# keyswitch.net
KiCad netlist of a schematic drawn in EAGLE
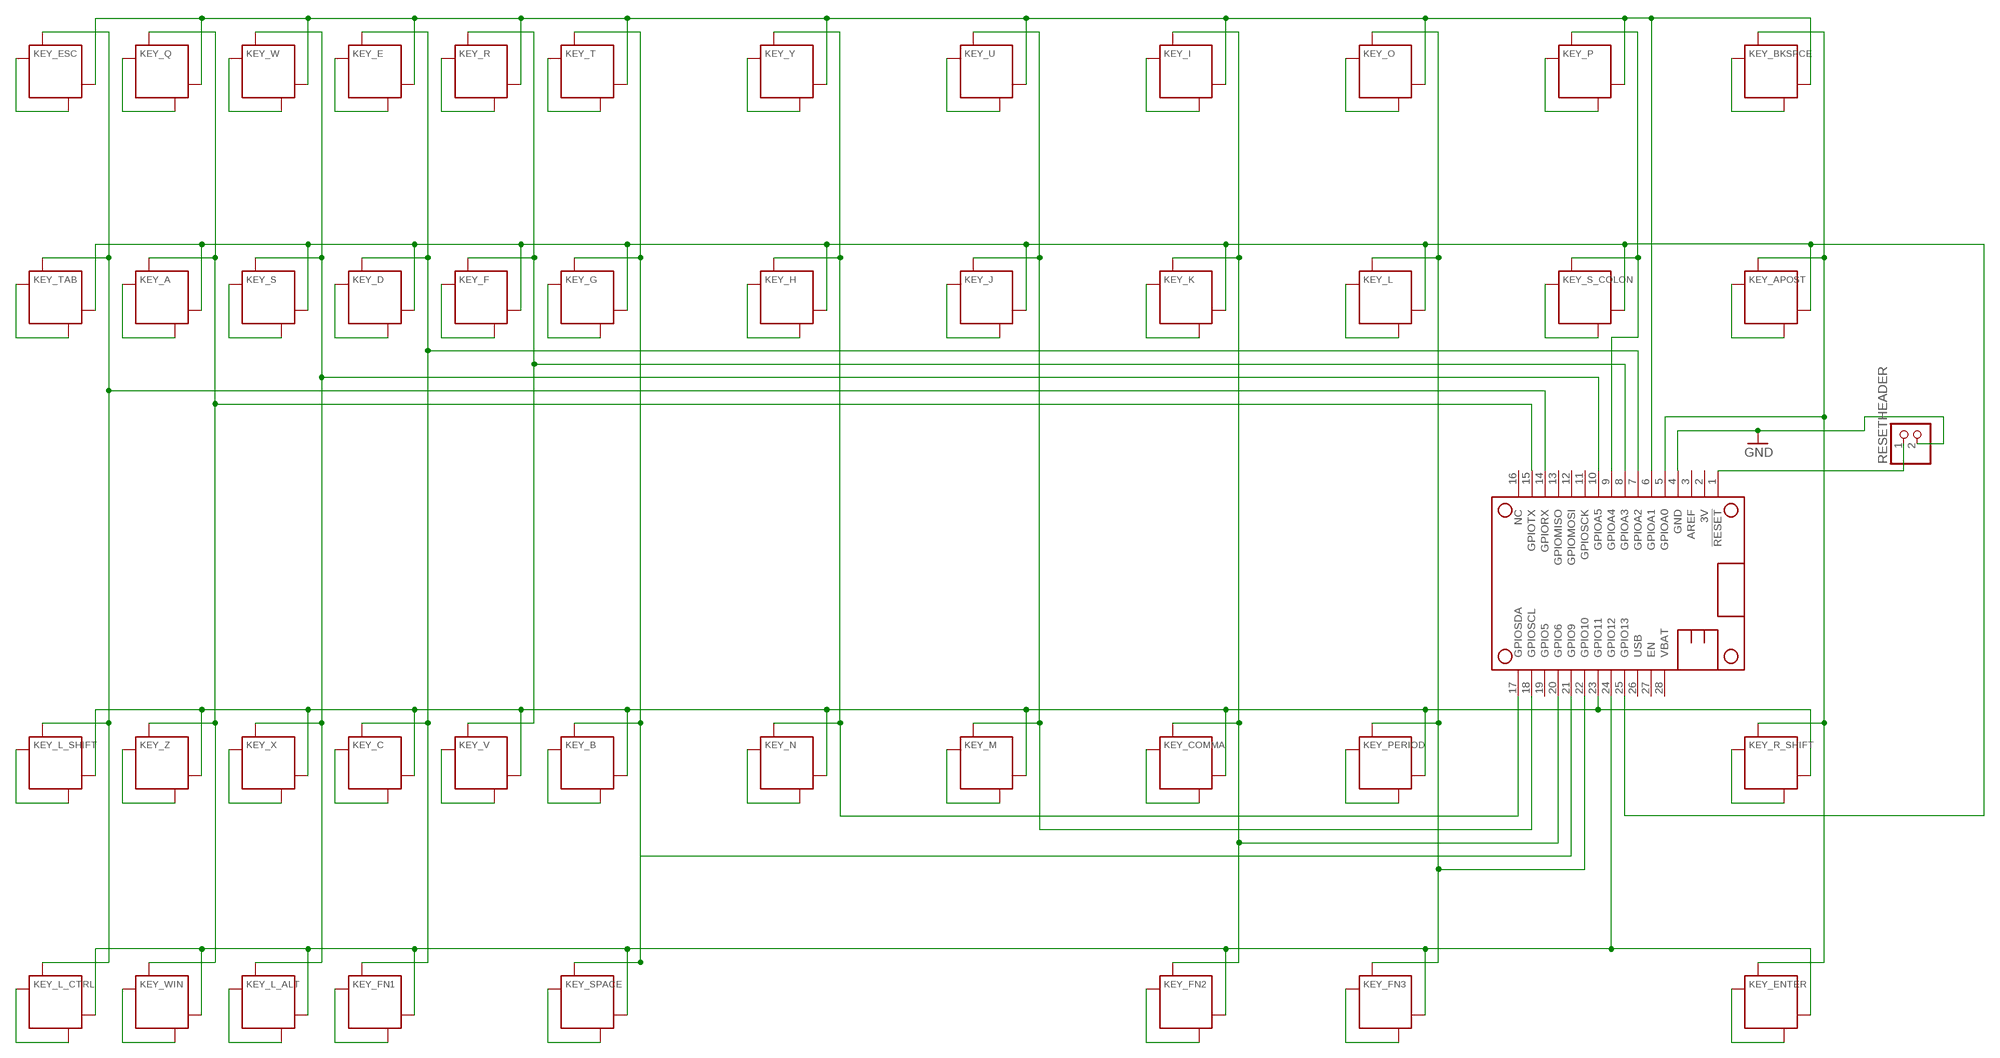
[diagram p0: schematic, sheet 1]

(export (version "E")
  (design (tool "Eeschema 10.0.6"))
  (components
    (comp (ref "FEATHER")
      (value "FEATHERWING_NODIM")
      (footprint "eagle-import:FEATHERWING_DIM")
      (libsource (lib "eagle-import") (part "FEATHERWING_NODIM"))
    )
    (comp (ref "KEY_A")
      (value "KEYSWITCH-DIODE-MX-1U-DIODE")
      (footprint "eagle-import:MX-1U-DIODE")
      (libsource (lib "eagle-import") (part "KEYSWITCH-DIODE-MX-1U-DIODE"))
    )
    (comp (ref "KEY_APOST")
      (value "KEYSWITCH-DIODE-MX-1U-DIODE")
      (footprint "eagle-import:MX-1U-DIODE")
      (libsource (lib "eagle-import") (part "KEYSWITCH-DIODE-MX-1U-DIODE"))
    )
    (comp (ref "KEY_B")
      (value "KEYSWITCH-DIODE-MX-1U-DIODE")
      (footprint "eagle-import:MX-1U-DIODE")
      (libsource (lib "eagle-import") (part "KEYSWITCH-DIODE-MX-1U-DIODE"))
    )
    (comp (ref "KEY_BKSPCE")
      (value "KEYSWITCH-DIODE-MX-1U-DIODE")
      (footprint "eagle-import:MX-1U-DIODE")
      (libsource (lib "eagle-import") (part "KEYSWITCH-DIODE-MX-1U-DIODE"))
    )
    (comp (ref "KEY_C")
      (value "KEYSWITCH-DIODE-MX-1U-DIODE")
      (footprint "eagle-import:MX-1U-DIODE")
      (libsource (lib "eagle-import") (part "KEYSWITCH-DIODE-MX-1U-DIODE"))
    )
    (comp (ref "KEY_COMMA")
      (value "KEYSWITCH-DIODE-MX-1U-DIODE")
      (footprint "eagle-import:MX-1U-DIODE")
      (libsource (lib "eagle-import") (part "KEYSWITCH-DIODE-MX-1U-DIODE"))
    )
    (comp (ref "KEY_D")
      (value "KEYSWITCH-DIODE-MX-1U-DIODE")
      (footprint "eagle-import:MX-1U-DIODE")
      (libsource (lib "eagle-import") (part "KEYSWITCH-DIODE-MX-1U-DIODE"))
    )
    (comp (ref "KEY_E")
      (value "KEYSWITCH-DIODE-MX-1U-DIODE")
      (footprint "eagle-import:MX-1U-DIODE")
      (libsource (lib "eagle-import") (part "KEYSWITCH-DIODE-MX-1U-DIODE"))
    )
    (comp (ref "KEY_ENTER")
      (value "KEYSWITCH-DIODE-MX-1U-DIODE")
      (footprint "eagle-import:MX-1U-DIODE")
      (libsource (lib "eagle-import") (part "KEYSWITCH-DIODE-MX-1U-DIODE"))
    )
    (comp (ref "KEY_ESC")
      (value "KEYSWITCH-DIODE-MX-1U-DIODE")
      (footprint "eagle-import:MX-1U-DIODE")
      (libsource (lib "eagle-import") (part "KEYSWITCH-DIODE-MX-1U-DIODE"))
    )
    (comp (ref "KEY_F")
      (value "KEYSWITCH-DIODE-MX-1U-DIODE")
      (footprint "eagle-import:MX-1U-DIODE")
      (libsource (lib "eagle-import") (part "KEYSWITCH-DIODE-MX-1U-DIODE"))
    )
    (comp (ref "KEY_FN1")
      (value "KEYSWITCH-DIODE-MX-1U-DIODE")
      (footprint "eagle-import:MX-1U-DIODE")
      (libsource (lib "eagle-import") (part "KEYSWITCH-DIODE-MX-1U-DIODE"))
    )
    (comp (ref "KEY_FN2")
      (value "KEYSWITCH-DIODE-MX-1U-DIODE")
      (footprint "eagle-import:MX-1U-DIODE")
      (libsource (lib "eagle-import") (part "KEYSWITCH-DIODE-MX-1U-DIODE"))
    )
    (comp (ref "KEY_FN3")
      (value "KEYSWITCH-DIODE-MX-1U-DIODE")
      (footprint "eagle-import:MX-1U-DIODE")
      (libsource (lib "eagle-import") (part "KEYSWITCH-DIODE-MX-1U-DIODE"))
    )
    (comp (ref "KEY_G")
      (value "KEYSWITCH-DIODE-MX-1U-DIODE")
      (footprint "eagle-import:MX-1U-DIODE")
      (libsource (lib "eagle-import") (part "KEYSWITCH-DIODE-MX-1U-DIODE"))
    )
    (comp (ref "KEY_H")
      (value "KEYSWITCH-DIODE-MX-1U-DIODE")
      (footprint "eagle-import:MX-1U-DIODE")
      (libsource (lib "eagle-import") (part "KEYSWITCH-DIODE-MX-1U-DIODE"))
    )
    (comp (ref "KEY_I")
      (value "KEYSWITCH-DIODE-MX-1U-DIODE")
      (footprint "eagle-import:MX-1U-DIODE")
      (libsource (lib "eagle-import") (part "KEYSWITCH-DIODE-MX-1U-DIODE"))
    )
    (comp (ref "KEY_J")
      (value "KEYSWITCH-DIODE-MX-1U-DIODE")
      (footprint "eagle-import:MX-1U-DIODE")
      (libsource (lib "eagle-import") (part "KEYSWITCH-DIODE-MX-1U-DIODE"))
    )
    (comp (ref "KEY_K")
      (value "KEYSWITCH-DIODE-MX-1U-DIODE")
      (footprint "eagle-import:MX-1U-DIODE")
      (libsource (lib "eagle-import") (part "KEYSWITCH-DIODE-MX-1U-DIODE"))
    )
    (comp (ref "KEY_L")
      (value "KEYSWITCH-DIODE-MX-1U-DIODE")
      (footprint "eagle-import:MX-1U-DIODE")
      (libsource (lib "eagle-import") (part "KEYSWITCH-DIODE-MX-1U-DIODE"))
    )
    (comp (ref "KEY_L_ALT")
      (value "KEYSWITCH-DIODE-MX-1U-DIODE")
      (footprint "eagle-import:MX-1U-DIODE")
      (libsource (lib "eagle-import") (part "KEYSWITCH-DIODE-MX-1U-DIODE"))
    )
    (comp (ref "KEY_L_CTRL")
      (value "KEYSWITCH-DIODE-MX-1U-DIODE")
      (footprint "eagle-import:MX-1U-DIODE")
      (libsource (lib "eagle-import") (part "KEYSWITCH-DIODE-MX-1U-DIODE"))
    )
    (comp (ref "KEY_L_SHIFT")
      (value "KEYSWITCH-DIODE-MX-1U-DIODE")
      (footprint "eagle-import:MX-1U-DIODE")
      (libsource (lib "eagle-import") (part "KEYSWITCH-DIODE-MX-1U-DIODE"))
    )
    (comp (ref "KEY_M")
      (value "KEYSWITCH-DIODE-MX-1U-DIODE")
      (footprint "eagle-import:MX-1U-DIODE")
      (libsource (lib "eagle-import") (part "KEYSWITCH-DIODE-MX-1U-DIODE"))
    )
    (comp (ref "KEY_N")
      (value "KEYSWITCH-DIODE-MX-1U-DIODE")
      (footprint "eagle-import:MX-1U-DIODE")
      (libsource (lib "eagle-import") (part "KEYSWITCH-DIODE-MX-1U-DIODE"))
    )
    (comp (ref "KEY_O")
      (value "KEYSWITCH-DIODE-MX-1U-DIODE")
      (footprint "eagle-import:MX-1U-DIODE")
      (libsource (lib "eagle-import") (part "KEYSWITCH-DIODE-MX-1U-DIODE"))
    )
    (comp (ref "KEY_P")
      (value "KEYSWITCH-DIODE-MX-1U-DIODE")
      (footprint "eagle-import:MX-1U-DIODE")
      (libsource (lib "eagle-import") (part "KEYSWITCH-DIODE-MX-1U-DIODE"))
    )
    (comp (ref "KEY_PERIOD")
      (value "KEYSWITCH-DIODE-MX-1U-DIODE")
      (footprint "eagle-import:MX-1U-DIODE")
      (libsource (lib "eagle-import") (part "KEYSWITCH-DIODE-MX-1U-DIODE"))
    )
    (comp (ref "KEY_Q")
      (value "KEYSWITCH-DIODE-MX-1U-DIODE")
      (footprint "eagle-import:MX-1U-DIODE")
      (libsource (lib "eagle-import") (part "KEYSWITCH-DIODE-MX-1U-DIODE"))
    )
    (comp (ref "KEY_R")
      (value "KEYSWITCH-DIODE-MX-1U-DIODE")
      (footprint "eagle-import:MX-1U-DIODE")
      (libsource (lib "eagle-import") (part "KEYSWITCH-DIODE-MX-1U-DIODE"))
    )
    (comp (ref "KEY_R_SHIFT")
      (value "KEYSWITCH-DIODE-MX-1U-DIODE")
      (footprint "eagle-import:MX-1U-DIODE")
      (libsource (lib "eagle-import") (part "KEYSWITCH-DIODE-MX-1U-DIODE"))
    )
    (comp (ref "KEY_S")
      (value "KEYSWITCH-DIODE-MX-1U-DIODE")
      (footprint "eagle-import:MX-1U-DIODE")
      (libsource (lib "eagle-import") (part "KEYSWITCH-DIODE-MX-1U-DIODE"))
    )
    (comp (ref "KEY_SPACE")
      (value "KEYSWITCH-DIODE-MX-1U-DIODE")
      (footprint "eagle-import:MX-1U-DIODE")
      (libsource (lib "eagle-import") (part "KEYSWITCH-DIODE-MX-1U-DIODE"))
    )
    (comp (ref "KEY_S_COLON")
      (value "KEYSWITCH-DIODE-MX-1U-DIODE")
      (footprint "eagle-import:MX-1U-DIODE")
      (libsource (lib "eagle-import") (part "KEYSWITCH-DIODE-MX-1U-DIODE"))
    )
    (comp (ref "KEY_T")
      (value "KEYSWITCH-DIODE-MX-1U-DIODE")
      (footprint "eagle-import:MX-1U-DIODE")
      (libsource (lib "eagle-import") (part "KEYSWITCH-DIODE-MX-1U-DIODE"))
    )
    (comp (ref "KEY_TAB")
      (value "KEYSWITCH-DIODE-MX-1U-DIODE")
      (footprint "eagle-import:MX-1U-DIODE")
      (libsource (lib "eagle-import") (part "KEYSWITCH-DIODE-MX-1U-DIODE"))
    )
    (comp (ref "KEY_U")
      (value "KEYSWITCH-DIODE-MX-1U-DIODE")
      (footprint "eagle-import:MX-1U-DIODE")
      (libsource (lib "eagle-import") (part "KEYSWITCH-DIODE-MX-1U-DIODE"))
    )
    (comp (ref "KEY_V")
      (value "KEYSWITCH-DIODE-MX-1U-DIODE")
      (footprint "eagle-import:MX-1U-DIODE")
      (libsource (lib "eagle-import") (part "KEYSWITCH-DIODE-MX-1U-DIODE"))
    )
    (comp (ref "KEY_W")
      (value "KEYSWITCH-DIODE-MX-1U-DIODE")
      (footprint "eagle-import:MX-1U-DIODE")
      (libsource (lib "eagle-import") (part "KEYSWITCH-DIODE-MX-1U-DIODE"))
    )
    (comp (ref "KEY_WIN")
      (value "KEYSWITCH-DIODE-MX-1U-DIODE")
      (footprint "eagle-import:MX-1U-DIODE")
      (libsource (lib "eagle-import") (part "KEYSWITCH-DIODE-MX-1U-DIODE"))
    )
    (comp (ref "KEY_X")
      (value "KEYSWITCH-DIODE-MX-1U-DIODE")
      (footprint "eagle-import:MX-1U-DIODE")
      (libsource (lib "eagle-import") (part "KEYSWITCH-DIODE-MX-1U-DIODE"))
    )
    (comp (ref "KEY_Y")
      (value "KEYSWITCH-DIODE-MX-1U-DIODE")
      (footprint "eagle-import:MX-1U-DIODE")
      (libsource (lib "eagle-import") (part "KEYSWITCH-DIODE-MX-1U-DIODE"))
    )
    (comp (ref "KEY_Z")
      (value "KEYSWITCH-DIODE-MX-1U-DIODE")
      (footprint "eagle-import:MX-1U-DIODE")
      (libsource (lib "eagle-import") (part "KEYSWITCH-DIODE-MX-1U-DIODE"))
    )
    (comp (ref "RESETHEADER")
      (value "PINHD-1X2")
      (footprint "eagle-import:1X02")
      (libsource (lib "eagle-import") (part "PINHD-1X2"))
    )
  )
  (nets
    (net (code "1") (name "/3V") (class "Default")
      (node (ref "FEATHER") (pin "2") (pinfunction "3V_2") (pintype "power_in"))
    )
    (net (code "2") (name "/USB") (class "Default")
      (node (ref "FEATHER") (pin "26") (pinfunction "USB_26") (pintype "power_in"))
    )
    (net (code "3") (name "/VBAT") (class "Default")
      (node (ref "FEATHER") (pin "28") (pinfunction "VBAT_28") (pintype "power_in"))
    )
    (net (code "4") (name "GND") (class "Default")
      (node (ref "FEATHER") (pin "4") (pinfunction "GND_4") (pintype "power_in"))
      (node (ref "RESETHEADER") (pin "2") (pinfunction "2_2") (pintype "passive"))
    )
    (net (code "5") (name "Net-(FEATHER-GPIO6)") (class "Default")
      (node (ref "FEATHER") (pin "20") (pinfunction "GPIO6_20") (pintype "bidirectional"))
      (node (ref "KEY_COMMA") (pin "MX2") (pinfunction "P1_MX2") (pintype "bidirectional"))
      (node (ref "KEY_FN2") (pin "MX2") (pinfunction "P1_MX2") (pintype "bidirectional"))
      (node (ref "KEY_I") (pin "MX2") (pinfunction "P1_MX2") (pintype "bidirectional"))
      (node (ref "KEY_K") (pin "MX2") (pinfunction "P1_MX2") (pintype "bidirectional"))
    )
    (net (code "6") (name "Net-(FEATHER-GPIO9)") (class "Default")
      (node (ref "FEATHER") (pin "21") (pinfunction "GPIO9_21") (pintype "bidirectional"))
      (node (ref "KEY_B") (pin "MX2") (pinfunction "P1_MX2") (pintype "bidirectional"))
      (node (ref "KEY_G") (pin "MX2") (pinfunction "P1_MX2") (pintype "bidirectional"))
      (node (ref "KEY_SPACE") (pin "MX2") (pinfunction "P1_MX2") (pintype "bidirectional"))
      (node (ref "KEY_T") (pin "MX2") (pinfunction "P1_MX2") (pintype "bidirectional"))
    )
    (net (code "7") (name "Net-(FEATHER-GPIO10)") (class "Default")
      (node (ref "FEATHER") (pin "22") (pinfunction "GPIO10_22") (pintype "bidirectional"))
      (node (ref "KEY_FN3") (pin "MX2") (pinfunction "P1_MX2") (pintype "bidirectional"))
      (node (ref "KEY_L") (pin "MX2") (pinfunction "P1_MX2") (pintype "bidirectional"))
      (node (ref "KEY_O") (pin "MX2") (pinfunction "P1_MX2") (pintype "bidirectional"))
      (node (ref "KEY_PERIOD") (pin "MX2") (pinfunction "P1_MX2") (pintype "bidirectional"))
    )
    (net (code "8") (name "Net-(FEATHER-GPIO11)") (class "Default")
      (node (ref "FEATHER") (pin "23") (pinfunction "GPIO11_23") (pintype "bidirectional"))
      (node (ref "KEY_B") (pin "D-") (pinfunction "D-_D-") (pintype "bidirectional"))
      (node (ref "KEY_C") (pin "D-") (pinfunction "D-_D-") (pintype "bidirectional"))
      (node (ref "KEY_COMMA") (pin "D-") (pinfunction "D-_D-") (pintype "bidirectional"))
      (node (ref "KEY_L_SHIFT") (pin "D-") (pinfunction "D-_D-") (pintype "bidirectional"))
      (node (ref "KEY_M") (pin "D-") (pinfunction "D-_D-") (pintype "bidirectional"))
      (node (ref "KEY_N") (pin "D-") (pinfunction "D-_D-") (pintype "bidirectional"))
      (node (ref "KEY_PERIOD") (pin "D-") (pinfunction "D-_D-") (pintype "bidirectional"))
      (node (ref "KEY_R_SHIFT") (pin "D-") (pinfunction "D-_D-") (pintype "bidirectional"))
      (node (ref "KEY_V") (pin "D-") (pinfunction "D-_D-") (pintype "bidirectional"))
      (node (ref "KEY_X") (pin "D-") (pinfunction "D-_D-") (pintype "bidirectional"))
      (node (ref "KEY_Z") (pin "D-") (pinfunction "D-_D-") (pintype "bidirectional"))
    )
    (net (code "9") (name "Net-(FEATHER-GPIO12)") (class "Default")
      (node (ref "FEATHER") (pin "24") (pinfunction "GPIO12_24") (pintype "bidirectional"))
      (node (ref "KEY_ENTER") (pin "D-") (pinfunction "D-_D-") (pintype "bidirectional"))
      (node (ref "KEY_FN1") (pin "D-") (pinfunction "D-_D-") (pintype "bidirectional"))
      (node (ref "KEY_FN2") (pin "D-") (pinfunction "D-_D-") (pintype "bidirectional"))
      (node (ref "KEY_FN3") (pin "D-") (pinfunction "D-_D-") (pintype "bidirectional"))
      (node (ref "KEY_L_ALT") (pin "D-") (pinfunction "D-_D-") (pintype "bidirectional"))
      (node (ref "KEY_L_CTRL") (pin "D-") (pinfunction "D-_D-") (pintype "bidirectional"))
      (node (ref "KEY_SPACE") (pin "D-") (pinfunction "D-_D-") (pintype "bidirectional"))
      (node (ref "KEY_WIN") (pin "D-") (pinfunction "D-_D-") (pintype "bidirectional"))
    )
    (net (code "10") (name "Net-(FEATHER-GPIO13)") (class "Default")
      (node (ref "FEATHER") (pin "25") (pinfunction "GPIO13_25") (pintype "bidirectional"))
      (node (ref "KEY_A") (pin "D-") (pinfunction "D-_D-") (pintype "bidirectional"))
      (node (ref "KEY_APOST") (pin "D-") (pinfunction "D-_D-") (pintype "bidirectional"))
      (node (ref "KEY_D") (pin "D-") (pinfunction "D-_D-") (pintype "bidirectional"))
      (node (ref "KEY_F") (pin "D-") (pinfunction "D-_D-") (pintype "bidirectional"))
      (node (ref "KEY_G") (pin "D-") (pinfunction "D-_D-") (pintype "bidirectional"))
      (node (ref "KEY_H") (pin "D-") (pinfunction "D-_D-") (pintype "bidirectional"))
      (node (ref "KEY_J") (pin "D-") (pinfunction "D-_D-") (pintype "bidirectional"))
      (node (ref "KEY_K") (pin "D-") (pinfunction "D-_D-") (pintype "bidirectional"))
      (node (ref "KEY_L") (pin "D-") (pinfunction "D-_D-") (pintype "bidirectional"))
      (node (ref "KEY_S") (pin "D-") (pinfunction "D-_D-") (pintype "bidirectional"))
      (node (ref "KEY_S_COLON") (pin "D-") (pinfunction "D-_D-") (pintype "bidirectional"))
      (node (ref "KEY_TAB") (pin "D-") (pinfunction "D-_D-") (pintype "bidirectional"))
    )
    (net (code "11") (name "Net-(FEATHER-GPIOA0)") (class "Default")
      (node (ref "FEATHER") (pin "5") (pinfunction "GPIOA0_5") (pintype "bidirectional"))
      (node (ref "KEY_APOST") (pin "MX2") (pinfunction "P1_MX2") (pintype "bidirectional"))
      (node (ref "KEY_BKSPCE") (pin "MX2") (pinfunction "P1_MX2") (pintype "bidirectional"))
      (node (ref "KEY_ENTER") (pin "MX2") (pinfunction "P1_MX2") (pintype "bidirectional"))
      (node (ref "KEY_R_SHIFT") (pin "MX2") (pinfunction "P1_MX2") (pintype "bidirectional"))
    )
    (net (code "12") (name "Net-(FEATHER-GPIOA1)") (class "Default")
      (node (ref "FEATHER") (pin "6") (pinfunction "GPIOA1_6") (pintype "bidirectional"))
      (node (ref "KEY_BKSPCE") (pin "D-") (pinfunction "D-_D-") (pintype "bidirectional"))
      (node (ref "KEY_E") (pin "D-") (pinfunction "D-_D-") (pintype "bidirectional"))
      (node (ref "KEY_ESC") (pin "D-") (pinfunction "D-_D-") (pintype "bidirectional"))
      (node (ref "KEY_I") (pin "D-") (pinfunction "D-_D-") (pintype "bidirectional"))
      (node (ref "KEY_O") (pin "D-") (pinfunction "D-_D-") (pintype "bidirectional"))
      (node (ref "KEY_P") (pin "D-") (pinfunction "D-_D-") (pintype "bidirectional"))
      (node (ref "KEY_Q") (pin "D-") (pinfunction "D-_D-") (pintype "bidirectional"))
      (node (ref "KEY_R") (pin "D-") (pinfunction "D-_D-") (pintype "bidirectional"))
      (node (ref "KEY_T") (pin "D-") (pinfunction "D-_D-") (pintype "bidirectional"))
      (node (ref "KEY_U") (pin "D-") (pinfunction "D-_D-") (pintype "bidirectional"))
      (node (ref "KEY_W") (pin "D-") (pinfunction "D-_D-") (pintype "bidirectional"))
      (node (ref "KEY_Y") (pin "D-") (pinfunction "D-_D-") (pintype "bidirectional"))
    )
    (net (code "13") (name "Net-(FEATHER-GPIOA2)") (class "Default")
      (node (ref "FEATHER") (pin "7") (pinfunction "GPIOA2_7") (pintype "bidirectional"))
      (node (ref "KEY_C") (pin "MX2") (pinfunction "P1_MX2") (pintype "bidirectional"))
      (node (ref "KEY_D") (pin "MX2") (pinfunction "P1_MX2") (pintype "bidirectional"))
      (node (ref "KEY_E") (pin "MX2") (pinfunction "P1_MX2") (pintype "bidirectional"))
      (node (ref "KEY_FN1") (pin "MX2") (pinfunction "P1_MX2") (pintype "bidirectional"))
    )
    (net (code "14") (name "Net-(FEATHER-GPIOA3)") (class "Default")
      (node (ref "FEATHER") (pin "8") (pinfunction "GPIOA3_8") (pintype "bidirectional"))
      (node (ref "KEY_F") (pin "MX2") (pinfunction "P1_MX2") (pintype "bidirectional"))
      (node (ref "KEY_R") (pin "MX2") (pinfunction "P1_MX2") (pintype "bidirectional"))
      (node (ref "KEY_V") (pin "MX2") (pinfunction "P1_MX2") (pintype "bidirectional"))
    )
    (net (code "15") (name "Net-(FEATHER-GPIOA4)") (class "Default")
      (node (ref "FEATHER") (pin "9") (pinfunction "GPIOA4_9") (pintype "bidirectional"))
      (node (ref "KEY_P") (pin "MX2") (pinfunction "P1_MX2") (pintype "bidirectional"))
      (node (ref "KEY_S_COLON") (pin "MX2") (pinfunction "P1_MX2") (pintype "bidirectional"))
    )
    (net (code "16") (name "Net-(FEATHER-GPIOA5)") (class "Default")
      (node (ref "FEATHER") (pin "10") (pinfunction "GPIOA5_10") (pintype "bidirectional"))
      (node (ref "KEY_L_ALT") (pin "MX2") (pinfunction "P1_MX2") (pintype "bidirectional"))
      (node (ref "KEY_S") (pin "MX2") (pinfunction "P1_MX2") (pintype "bidirectional"))
      (node (ref "KEY_W") (pin "MX2") (pinfunction "P1_MX2") (pintype "bidirectional"))
      (node (ref "KEY_X") (pin "MX2") (pinfunction "P1_MX2") (pintype "bidirectional"))
    )
    (net (code "17") (name "Net-(FEATHER-GPIORX)") (class "Default")
      (node (ref "FEATHER") (pin "14") (pinfunction "GPIORX_14") (pintype "bidirectional"))
      (node (ref "KEY_ESC") (pin "MX2") (pinfunction "P1_MX2") (pintype "bidirectional"))
      (node (ref "KEY_L_CTRL") (pin "MX2") (pinfunction "P1_MX2") (pintype "bidirectional"))
      (node (ref "KEY_L_SHIFT") (pin "MX2") (pinfunction "P1_MX2") (pintype "bidirectional"))
      (node (ref "KEY_TAB") (pin "MX2") (pinfunction "P1_MX2") (pintype "bidirectional"))
    )
    (net (code "18") (name "Net-(FEATHER-GPIOSCL)") (class "Default")
      (node (ref "FEATHER") (pin "18") (pinfunction "GPIOSCL_18") (pintype "bidirectional"))
      (node (ref "KEY_J") (pin "MX2") (pinfunction "P1_MX2") (pintype "bidirectional"))
      (node (ref "KEY_M") (pin "MX2") (pinfunction "P1_MX2") (pintype "bidirectional"))
      (node (ref "KEY_U") (pin "MX2") (pinfunction "P1_MX2") (pintype "bidirectional"))
    )
    (net (code "19") (name "Net-(FEATHER-GPIOSDA)") (class "Default")
      (node (ref "FEATHER") (pin "17") (pinfunction "GPIOSDA_17") (pintype "bidirectional"))
      (node (ref "KEY_H") (pin "MX2") (pinfunction "P1_MX2") (pintype "bidirectional"))
      (node (ref "KEY_N") (pin "MX2") (pinfunction "P1_MX2") (pintype "bidirectional"))
      (node (ref "KEY_Y") (pin "MX2") (pinfunction "P1_MX2") (pintype "bidirectional"))
    )
    (net (code "20") (name "Net-(FEATHER-GPIOTX)") (class "Default")
      (node (ref "FEATHER") (pin "15") (pinfunction "GPIOTX_15") (pintype "bidirectional"))
      (node (ref "KEY_A") (pin "MX2") (pinfunction "P1_MX2") (pintype "bidirectional"))
      (node (ref "KEY_Q") (pin "MX2") (pinfunction "P1_MX2") (pintype "bidirectional"))
      (node (ref "KEY_WIN") (pin "MX2") (pinfunction "P1_MX2") (pintype "bidirectional"))
      (node (ref "KEY_Z") (pin "MX2") (pinfunction "P1_MX2") (pintype "bidirectional"))
    )
    (net (code "21") (name "Net-(FEATHER-~{RESET})") (class "Default")
      (node (ref "FEATHER") (pin "1") (pinfunction "~{RESET}_1") (pintype "input"))
      (node (ref "RESETHEADER") (pin "1") (pinfunction "1_1") (pintype "passive"))
    )
    (net (code "22") (name "Net-(KEY_A-P0)") (class "Default")
      (node (ref "KEY_A") (pin "D+") (pinfunction "D+_D+") (pintype "bidirectional"))
      (node (ref "KEY_A") (pin "MX1") (pinfunction "P0_MX1") (pintype "bidirectional"))
    )
    (net (code "23") (name "Net-(KEY_APOST-P0)") (class "Default")
      (node (ref "KEY_APOST") (pin "D+") (pinfunction "D+_D+") (pintype "bidirectional"))
      (node (ref "KEY_APOST") (pin "MX1") (pinfunction "P0_MX1") (pintype "bidirectional"))
    )
    (net (code "24") (name "Net-(KEY_B-P0)") (class "Default")
      (node (ref "KEY_B") (pin "D+") (pinfunction "D+_D+") (pintype "bidirectional"))
      (node (ref "KEY_B") (pin "MX1") (pinfunction "P0_MX1") (pintype "bidirectional"))
    )
    (net (code "25") (name "Net-(KEY_BKSPCE-P0)") (class "Default")
      (node (ref "KEY_BKSPCE") (pin "D+") (pinfunction "D+_D+") (pintype "bidirectional"))
      (node (ref "KEY_BKSPCE") (pin "MX1") (pinfunction "P0_MX1") (pintype "bidirectional"))
    )
    (net (code "26") (name "Net-(KEY_C-P0)") (class "Default")
      (node (ref "KEY_C") (pin "D+") (pinfunction "D+_D+") (pintype "bidirectional"))
      (node (ref "KEY_C") (pin "MX1") (pinfunction "P0_MX1") (pintype "bidirectional"))
    )
    (net (code "27") (name "Net-(KEY_COMMA-P0)") (class "Default")
      (node (ref "KEY_COMMA") (pin "D+") (pinfunction "D+_D+") (pintype "bidirectional"))
      (node (ref "KEY_COMMA") (pin "MX1") (pinfunction "P0_MX1") (pintype "bidirectional"))
    )
    (net (code "28") (name "Net-(KEY_D-P0)") (class "Default")
      (node (ref "KEY_D") (pin "D+") (pinfunction "D+_D+") (pintype "bidirectional"))
      (node (ref "KEY_D") (pin "MX1") (pinfunction "P0_MX1") (pintype "bidirectional"))
    )
    (net (code "29") (name "Net-(KEY_E-P0)") (class "Default")
      (node (ref "KEY_E") (pin "D+") (pinfunction "D+_D+") (pintype "bidirectional"))
      (node (ref "KEY_E") (pin "MX1") (pinfunction "P0_MX1") (pintype "bidirectional"))
    )
    (net (code "30") (name "Net-(KEY_ENTER-P0)") (class "Default")
      (node (ref "KEY_ENTER") (pin "D+") (pinfunction "D+_D+") (pintype "bidirectional"))
      (node (ref "KEY_ENTER") (pin "MX1") (pinfunction "P0_MX1") (pintype "bidirectional"))
    )
    (net (code "31") (name "Net-(KEY_ESC-P0)") (class "Default")
      (node (ref "KEY_ESC") (pin "D+") (pinfunction "D+_D+") (pintype "bidirectional"))
      (node (ref "KEY_ESC") (pin "MX1") (pinfunction "P0_MX1") (pintype "bidirectional"))
    )
    (net (code "32") (name "Net-(KEY_F-P0)") (class "Default")
      (node (ref "KEY_F") (pin "D+") (pinfunction "D+_D+") (pintype "bidirectional"))
      (node (ref "KEY_F") (pin "MX1") (pinfunction "P0_MX1") (pintype "bidirectional"))
    )
    (net (code "33") (name "Net-(KEY_FN1-P0)") (class "Default")
      (node (ref "KEY_FN1") (pin "D+") (pinfunction "D+_D+") (pintype "bidirectional"))
      (node (ref "KEY_FN1") (pin "MX1") (pinfunction "P0_MX1") (pintype "bidirectional"))
    )
    (net (code "34") (name "Net-(KEY_FN2-P0)") (class "Default")
      (node (ref "KEY_FN2") (pin "D+") (pinfunction "D+_D+") (pintype "bidirectional"))
      (node (ref "KEY_FN2") (pin "MX1") (pinfunction "P0_MX1") (pintype "bidirectional"))
    )
    (net (code "35") (name "Net-(KEY_FN3-P0)") (class "Default")
      (node (ref "KEY_FN3") (pin "D+") (pinfunction "D+_D+") (pintype "bidirectional"))
      (node (ref "KEY_FN3") (pin "MX1") (pinfunction "P0_MX1") (pintype "bidirectional"))
    )
    (net (code "36") (name "Net-(KEY_G-P0)") (class "Default")
      (node (ref "KEY_G") (pin "D+") (pinfunction "D+_D+") (pintype "bidirectional"))
      (node (ref "KEY_G") (pin "MX1") (pinfunction "P0_MX1") (pintype "bidirectional"))
    )
    (net (code "37") (name "Net-(KEY_H-P0)") (class "Default")
      (node (ref "KEY_H") (pin "D+") (pinfunction "D+_D+") (pintype "bidirectional"))
      (node (ref "KEY_H") (pin "MX1") (pinfunction "P0_MX1") (pintype "bidirectional"))
    )
    (net (code "38") (name "Net-(KEY_I-P0)") (class "Default")
      (node (ref "KEY_I") (pin "D+") (pinfunction "D+_D+") (pintype "bidirectional"))
      (node (ref "KEY_I") (pin "MX1") (pinfunction "P0_MX1") (pintype "bidirectional"))
    )
    (net (code "39") (name "Net-(KEY_J-P0)") (class "Default")
      (node (ref "KEY_J") (pin "D+") (pinfunction "D+_D+") (pintype "bidirectional"))
      (node (ref "KEY_J") (pin "MX1") (pinfunction "P0_MX1") (pintype "bidirectional"))
    )
    (net (code "40") (name "Net-(KEY_K-P0)") (class "Default")
      (node (ref "KEY_K") (pin "D+") (pinfunction "D+_D+") (pintype "bidirectional"))
      (node (ref "KEY_K") (pin "MX1") (pinfunction "P0_MX1") (pintype "bidirectional"))
    )
    (net (code "41") (name "Net-(KEY_L-P0)") (class "Default")
      (node (ref "KEY_L") (pin "D+") (pinfunction "D+_D+") (pintype "bidirectional"))
      (node (ref "KEY_L") (pin "MX1") (pinfunction "P0_MX1") (pintype "bidirectional"))
    )
    (net (code "42") (name "Net-(KEY_L_ALT-P0)") (class "Default")
      (node (ref "KEY_L_ALT") (pin "D+") (pinfunction "D+_D+") (pintype "bidirectional"))
      (node (ref "KEY_L_ALT") (pin "MX1") (pinfunction "P0_MX1") (pintype "bidirectional"))
    )
    (net (code "43") (name "Net-(KEY_L_CTRL-P0)") (class "Default")
      (node (ref "KEY_L_CTRL") (pin "D+") (pinfunction "D+_D+") (pintype "bidirectional"))
      (node (ref "KEY_L_CTRL") (pin "MX1") (pinfunction "P0_MX1") (pintype "bidirectional"))
    )
    (net (code "44") (name "Net-(KEY_L_SHIFT-P0)") (class "Default")
      (node (ref "KEY_L_SHIFT") (pin "D+") (pinfunction "D+_D+") (pintype "bidirectional"))
      (node (ref "KEY_L_SHIFT") (pin "MX1") (pinfunction "P0_MX1") (pintype "bidirectional"))
    )
    (net (code "45") (name "Net-(KEY_M-P0)") (class "Default")
      (node (ref "KEY_M") (pin "D+") (pinfunction "D+_D+") (pintype "bidirectional"))
      (node (ref "KEY_M") (pin "MX1") (pinfunction "P0_MX1") (pintype "bidirectional"))
    )
    (net (code "46") (name "Net-(KEY_N-P0)") (class "Default")
      (node (ref "KEY_N") (pin "D+") (pinfunction "D+_D+") (pintype "bidirectional"))
      (node (ref "KEY_N") (pin "MX1") (pinfunction "P0_MX1") (pintype "bidirectional"))
    )
    (net (code "47") (name "Net-(KEY_O-P0)") (class "Default")
      (node (ref "KEY_O") (pin "D+") (pinfunction "D+_D+") (pintype "bidirectional"))
      (node (ref "KEY_O") (pin "MX1") (pinfunction "P0_MX1") (pintype "bidirectional"))
    )
    (net (code "48") (name "Net-(KEY_P-P0)") (class "Default")
      (node (ref "KEY_P") (pin "D+") (pinfunction "D+_D+") (pintype "bidirectional"))
      (node (ref "KEY_P") (pin "MX1") (pinfunction "P0_MX1") (pintype "bidirectional"))
    )
    (net (code "49") (name "Net-(KEY_PERIOD-P0)") (class "Default")
      (node (ref "KEY_PERIOD") (pin "D+") (pinfunction "D+_D+") (pintype "bidirectional"))
      (node (ref "KEY_PERIOD") (pin "MX1") (pinfunction "P0_MX1") (pintype "bidirectional"))
    )
    (net (code "50") (name "Net-(KEY_Q-P0)") (class "Default")
      (node (ref "KEY_Q") (pin "D+") (pinfunction "D+_D+") (pintype "bidirectional"))
      (node (ref "KEY_Q") (pin "MX1") (pinfunction "P0_MX1") (pintype "bidirectional"))
    )
    (net (code "51") (name "Net-(KEY_R-P0)") (class "Default")
      (node (ref "KEY_R") (pin "D+") (pinfunction "D+_D+") (pintype "bidirectional"))
      (node (ref "KEY_R") (pin "MX1") (pinfunction "P0_MX1") (pintype "bidirectional"))
    )
    (net (code "52") (name "Net-(KEY_R_SHIFT-P0)") (class "Default")
      (node (ref "KEY_R_SHIFT") (pin "D+") (pinfunction "D+_D+") (pintype "bidirectional"))
      (node (ref "KEY_R_SHIFT") (pin "MX1") (pinfunction "P0_MX1") (pintype "bidirectional"))
    )
    (net (code "53") (name "Net-(KEY_S-P0)") (class "Default")
      (node (ref "KEY_S") (pin "D+") (pinfunction "D+_D+") (pintype "bidirectional"))
      (node (ref "KEY_S") (pin "MX1") (pinfunction "P0_MX1") (pintype "bidirectional"))
    )
    (net (code "54") (name "Net-(KEY_SPACE-P0)") (class "Default")
      (node (ref "KEY_SPACE") (pin "D+") (pinfunction "D+_D+") (pintype "bidirectional"))
      (node (ref "KEY_SPACE") (pin "MX1") (pinfunction "P0_MX1") (pintype "bidirectional"))
    )
    (net (code "55") (name "Net-(KEY_S_COLON-P0)") (class "Default")
      (node (ref "KEY_S_COLON") (pin "D+") (pinfunction "D+_D+") (pintype "bidirectional"))
      (node (ref "KEY_S_COLON") (pin "MX1") (pinfunction "P0_MX1") (pintype "bidirectional"))
    )
    (net (code "56") (name "Net-(KEY_T-P0)") (class "Default")
      (node (ref "KEY_T") (pin "D+") (pinfunction "D+_D+") (pintype "bidirectional"))
      (node (ref "KEY_T") (pin "MX1") (pinfunction "P0_MX1") (pintype "bidirectional"))
    )
    (net (code "57") (name "Net-(KEY_TAB-P0)") (class "Default")
      (node (ref "KEY_TAB") (pin "D+") (pinfunction "D+_D+") (pintype "bidirectional"))
      (node (ref "KEY_TAB") (pin "MX1") (pinfunction "P0_MX1") (pintype "bidirectional"))
    )
    (net (code "58") (name "Net-(KEY_U-P0)") (class "Default")
      (node (ref "KEY_U") (pin "D+") (pinfunction "D+_D+") (pintype "bidirectional"))
      (node (ref "KEY_U") (pin "MX1") (pinfunction "P0_MX1") (pintype "bidirectional"))
    )
    (net (code "59") (name "Net-(KEY_V-P0)") (class "Default")
      (node (ref "KEY_V") (pin "D+") (pinfunction "D+_D+") (pintype "bidirectional"))
      (node (ref "KEY_V") (pin "MX1") (pinfunction "P0_MX1") (pintype "bidirectional"))
    )
    (net (code "60") (name "Net-(KEY_W-P0)") (class "Default")
      (node (ref "KEY_W") (pin "D+") (pinfunction "D+_D+") (pintype "bidirectional"))
      (node (ref "KEY_W") (pin "MX1") (pinfunction "P0_MX1") (pintype "bidirectional"))
    )
    (net (code "61") (name "Net-(KEY_WIN-P0)") (class "Default")
      (node (ref "KEY_WIN") (pin "D+") (pinfunction "D+_D+") (pintype "bidirectional"))
      (node (ref "KEY_WIN") (pin "MX1") (pinfunction "P0_MX1") (pintype "bidirectional"))
    )
    (net (code "62") (name "Net-(KEY_X-P0)") (class "Default")
      (node (ref "KEY_X") (pin "D+") (pinfunction "D+_D+") (pintype "bidirectional"))
      (node (ref "KEY_X") (pin "MX1") (pinfunction "P0_MX1") (pintype "bidirectional"))
    )
    (net (code "63") (name "Net-(KEY_Y-P0)") (class "Default")
      (node (ref "KEY_Y") (pin "D+") (pinfunction "D+_D+") (pintype "bidirectional"))
      (node (ref "KEY_Y") (pin "MX1") (pinfunction "P0_MX1") (pintype "bidirectional"))
    )
    (net (code "64") (name "Net-(KEY_Z-P0)") (class "Default")
      (node (ref "KEY_Z") (pin "D+") (pinfunction "D+_D+") (pintype "bidirectional"))
      (node (ref "KEY_Z") (pin "MX1") (pinfunction "P0_MX1") (pintype "bidirectional"))
    )
    (net (code "65") (name "unconnected-(FEATHER-AREF-Pad3)") (class "Default")
      (node (ref "FEATHER") (pin "3") (pinfunction "AREF_3") (pintype "passive"))
    )
    (net (code "66") (name "unconnected-(FEATHER-EN-Pad27)") (class "Default")
      (node (ref "FEATHER") (pin "27") (pinfunction "EN_27") (pintype "passive"))
    )
    (net (code "67") (name "unconnected-(FEATHER-GPIO5-Pad19)") (class "Default")
      (node (ref "FEATHER") (pin "19") (pinfunction "GPIO5_19") (pintype "bidirectional"))
    )
    (net (code "68") (name "unconnected-(FEATHER-GPIOMISO-Pad13)") (class "Default")
      (node (ref "FEATHER") (pin "13") (pinfunction "GPIOMISO_13") (pintype "bidirectional"))
    )
    (net (code "69") (name "unconnected-(FEATHER-GPIOMOSI-Pad12)") (class "Default")
      (node (ref "FEATHER") (pin "12") (pinfunction "GPIOMOSI_12") (pintype "bidirectional"))
    )
    (net (code "70") (name "unconnected-(FEATHER-GPIOSCK-Pad11)") (class "Default")
      (node (ref "FEATHER") (pin "11") (pinfunction "GPIOSCK_11") (pintype "bidirectional"))
    )
    (net (code "71") (name "unconnected-(FEATHER-NC-Pad16)") (class "Default")
      (node (ref "FEATHER") (pin "16") (pinfunction "NC_16") (pintype "passive"))
    )
  )
)
